# LM3916.net
KiCad netlist of a schematic drawn in EAGLE
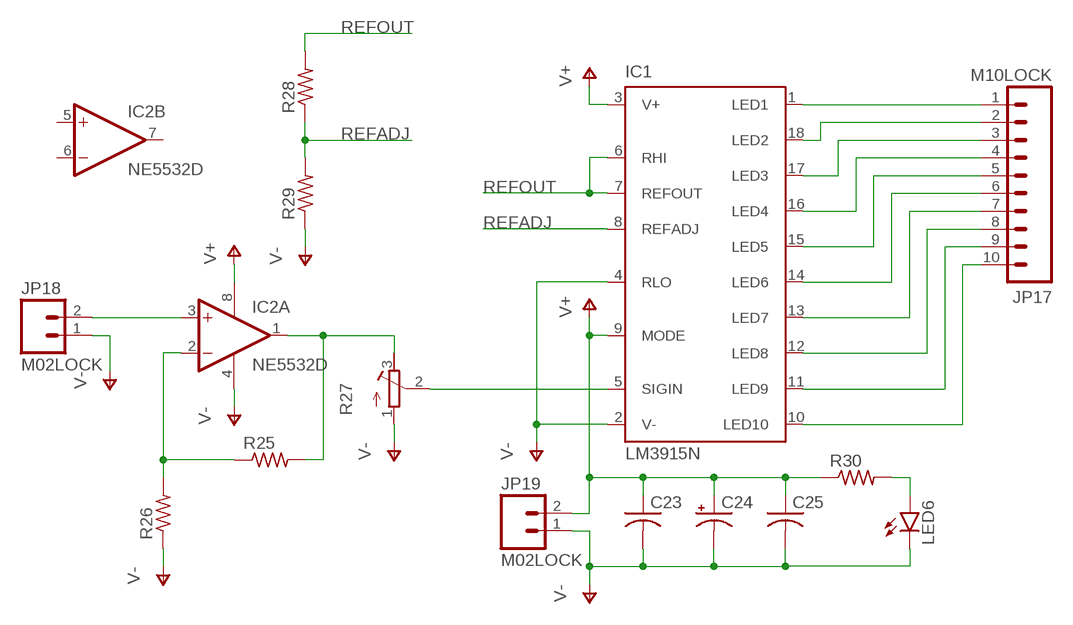
[diagram p0: schematic, sheet 1]

(export (version "E")
  (design (tool "Eeschema 10.0.6"))
  (components
    (comp (ref "C23")
      (value "C-USC0805")
      (footprint "eagle-import:C0805")
      (libsource (lib "eagle-import") (part "C-USC0805"))
    )
    (comp (ref "C24")
      (value "CPOL-USE2-5")
      (footprint "eagle-import:E2-5")
      (libsource (lib "eagle-import") (part "CPOL-USE2-5"))
    )
    (comp (ref "C25")
      (value "C-USC0805")
      (footprint "eagle-import:C0805")
      (libsource (lib "eagle-import") (part "C-USC0805"))
    )
    (comp (ref "IC1")
      (value "LM3915N")
      (footprint "eagle-import:DIL18")
      (libsource (lib "eagle-import") (part "LM391N5"))
    )
    (comp (ref "IC2")
      (value "NE5532D")
      (footprint "eagle-import:SO08")
      (libsource (lib "eagle-import") (part "NE5532D"))
    )
    (comp (ref "JP17")
      (value "M10LOCK")
      (footprint "eagle-import:1X10_LOCK")
      (libsource (lib "eagle-import") (part "M10LOCK"))
    )
    (comp (ref "JP18")
      (value "M02LOCK")
      (footprint "eagle-import:1X02_LOCK")
      (libsource (lib "eagle-import") (part "M02LOCK"))
    )
    (comp (ref "JP19")
      (value "M02LOCK")
      (footprint "eagle-import:1X02_LOCK")
      (libsource (lib "eagle-import") (part "M02LOCK"))
    )
    (comp (ref "LED6")
      (value "LED1206")
      (footprint "eagle-import:LED-1206")
      (libsource (lib "eagle-import") (part "LED1206"))
    )
    (comp (ref "R25")
      (value "R-US_R0805")
      (footprint "eagle-import:R0805")
      (libsource (lib "eagle-import") (part "R-US_R0805"))
    )
    (comp (ref "R26")
      (value "R-US_R0805")
      (footprint "eagle-import:R0805")
      (libsource (lib "eagle-import") (part "R-US_R0805"))
    )
    (comp (ref "R27")
      (value "R-TRIMM64W")
      (footprint "eagle-import:RTRIM64W")
      (libsource (lib "eagle-import") (part "R-TRIMM64W"))
    )
    (comp (ref "R28")
      (value "R-US_R0805")
      (footprint "eagle-import:R0805")
      (libsource (lib "eagle-import") (part "R-US_R0805"))
    )
    (comp (ref "R29")
      (value "R-US_R0805")
      (footprint "eagle-import:R0805")
      (libsource (lib "eagle-import") (part "R-US_R0805"))
    )
    (comp (ref "R30")
      (value "R-US_R0805")
      (footprint "eagle-import:R0805")
      (libsource (lib "eagle-import") (part "R-US_R0805"))
    )
  )
  (nets
    (net (code "1") (name "/REFADJ") (class "Default")
      (node (ref "IC1") (pin "8") (pinfunction "REFADJ_8") (pintype "passive"))
      (node (ref "R28") (pin "1") (pinfunction "1_1") (pintype "passive"))
      (node (ref "R29") (pin "2") (pinfunction "2_2") (pintype "passive"))
    )
    (net (code "2") (name "/REFOUT") (class "Default")
      (node (ref "IC1") (pin "6") (pinfunction "RHI_6") (pintype "input"))
      (node (ref "IC1") (pin "7") (pinfunction "REFOUT_7") (pintype "output"))
      (node (ref "R28") (pin "2") (pinfunction "2_2") (pintype "passive"))
    )
    (net (code "3") (name "Net-(IC1-LED1)") (class "Default")
      (node (ref "IC1") (pin "1") (pinfunction "LED1_1") (pintype "output"))
      (node (ref "JP17") (pin "1") (pinfunction "1_1") (pintype "passive"))
    )
    (net (code "4") (name "Net-(IC1-LED2)") (class "Default")
      (node (ref "IC1") (pin "18") (pinfunction "LED2_18") (pintype "output"))
      (node (ref "JP17") (pin "2") (pinfunction "2_2") (pintype "passive"))
    )
    (net (code "5") (name "Net-(IC1-LED3)") (class "Default")
      (node (ref "IC1") (pin "17") (pinfunction "LED3_17") (pintype "output"))
      (node (ref "JP17") (pin "3") (pinfunction "3_3") (pintype "passive"))
    )
    (net (code "6") (name "Net-(IC1-LED4)") (class "Default")
      (node (ref "IC1") (pin "16") (pinfunction "LED4_16") (pintype "output"))
      (node (ref "JP17") (pin "4") (pinfunction "4_4") (pintype "passive"))
    )
    (net (code "7") (name "Net-(IC1-LED5)") (class "Default")
      (node (ref "IC1") (pin "15") (pinfunction "LED5_15") (pintype "output"))
      (node (ref "JP17") (pin "5") (pinfunction "5_5") (pintype "passive"))
    )
    (net (code "8") (name "Net-(IC1-LED6)") (class "Default")
      (node (ref "IC1") (pin "14") (pinfunction "LED6_14") (pintype "output"))
      (node (ref "JP17") (pin "6") (pinfunction "6_6") (pintype "passive"))
    )
    (net (code "9") (name "Net-(IC1-LED7)") (class "Default")
      (node (ref "IC1") (pin "13") (pinfunction "LED7_13") (pintype "output"))
      (node (ref "JP17") (pin "7") (pinfunction "7_7") (pintype "passive"))
    )
    (net (code "10") (name "Net-(IC1-LED8)") (class "Default")
      (node (ref "IC1") (pin "12") (pinfunction "LED8_12") (pintype "output"))
      (node (ref "JP17") (pin "8") (pinfunction "8_8") (pintype "passive"))
    )
    (net (code "11") (name "Net-(IC1-LED9)") (class "Default")
      (node (ref "IC1") (pin "11") (pinfunction "LED9_11") (pintype "output"))
      (node (ref "JP17") (pin "9") (pinfunction "9_9") (pintype "passive"))
    )
    (net (code "12") (name "Net-(IC1-LED10)") (class "Default")
      (node (ref "IC1") (pin "10") (pinfunction "LED10_10") (pintype "output"))
      (node (ref "JP17") (pin "10") (pinfunction "10_10") (pintype "passive"))
    )
    (net (code "13") (name "Net-(IC1-SIGIN)") (class "Default")
      (node (ref "IC1") (pin "5") (pinfunction "SIGIN_5") (pintype "input"))
      (node (ref "R27") (pin "2") (pinfunction "S_2") (pintype "passive"))
    )
    (net (code "14") (name "Net-(IC2A-+IN)") (class "Default")
      (node (ref "IC2") (pin "3") (pinfunction "+IN_3") (pintype "input"))
      (node (ref "JP18") (pin "2") (pinfunction "2_2") (pintype "passive"))
    )
    (net (code "15") (name "Net-(IC2A--IN)") (class "Default")
      (node (ref "IC2") (pin "2") (pinfunction "-IN_2") (pintype "input"))
      (node (ref "R25") (pin "1") (pinfunction "1_1") (pintype "passive"))
      (node (ref "R26") (pin "2") (pinfunction "2_2") (pintype "passive"))
    )
    (net (code "16") (name "Net-(IC2A-OUT)") (class "Default")
      (node (ref "IC2") (pin "1") (pinfunction "OUT_1") (pintype "output"))
      (node (ref "R25") (pin "2") (pinfunction "2_2") (pintype "passive"))
      (node (ref "R27") (pin "3") (pinfunction "E_3") (pintype "passive"))
    )
    (net (code "17") (name "Net-(LED6-PadA)") (class "Default")
      (node (ref "LED6") (pin "A") (pinfunction "A_A") (pintype "passive"))
      (node (ref "R30") (pin "2") (pinfunction "2_2") (pintype "passive"))
    )
    (net (code "18") (name "V+") (class "Default")
      (node (ref "C23") (pin "1") (pinfunction "1_1") (pintype "passive"))
      (node (ref "C24") (pin "+") (pinfunction "+_+") (pintype "passive"))
      (node (ref "C25") (pin "1") (pinfunction "1_1") (pintype "passive"))
      (node (ref "IC1") (pin "3") (pinfunction "V+_3") (pintype "power_in"))
      (node (ref "IC1") (pin "9") (pinfunction "MODE_9") (pintype "input"))
      (node (ref "IC2") (pin "8") (pinfunction "V+_8") (pintype "power_in"))
      (node (ref "JP19") (pin "2") (pinfunction "2_2") (pintype "passive"))
      (node (ref "R30") (pin "1") (pinfunction "1_1") (pintype "passive"))
    )
    (net (code "19") (name "V-") (class "Default")
      (node (ref "C23") (pin "2") (pinfunction "2_2") (pintype "passive"))
      (node (ref "C24") (pin "-") (pinfunction "-_-") (pintype "passive"))
      (node (ref "C25") (pin "2") (pinfunction "2_2") (pintype "passive"))
      (node (ref "IC1") (pin "2") (pinfunction "V-_2") (pintype "power_in"))
      (node (ref "IC1") (pin "4") (pinfunction "RLO_4") (pintype "input"))
      (node (ref "IC2") (pin "4") (pinfunction "V-_4") (pintype "power_in"))
      (node (ref "JP18") (pin "1") (pinfunction "1_1") (pintype "passive"))
      (node (ref "JP19") (pin "1") (pinfunction "1_1") (pintype "passive"))
      (node (ref "LED6") (pin "C") (pinfunction "C_C") (pintype "passive"))
      (node (ref "R26") (pin "1") (pinfunction "1_1") (pintype "passive"))
      (node (ref "R27") (pin "1") (pinfunction "A_1") (pintype "passive"))
      (node (ref "R29") (pin "1") (pinfunction "1_1") (pintype "passive"))
    )
    (net (code "20") (name "unconnected-(IC2B-+IN-Pad5)") (class "Default")
      (node (ref "IC2") (pin "5") (pinfunction "+IN_5") (pintype "input"))
    )
    (net (code "21") (name "unconnected-(IC2B--IN-Pad6)") (class "Default")
      (node (ref "IC2") (pin "6") (pinfunction "-IN_6") (pintype "input"))
    )
    (net (code "22") (name "unconnected-(IC2B-OUT-Pad7)") (class "Default")
      (node (ref "IC2") (pin "7") (pinfunction "OUT_7") (pintype "output"))
    )
  )
)
